# aMazeGarden_schematic.net
KiCad netlist of a schematic drawn in EAGLE
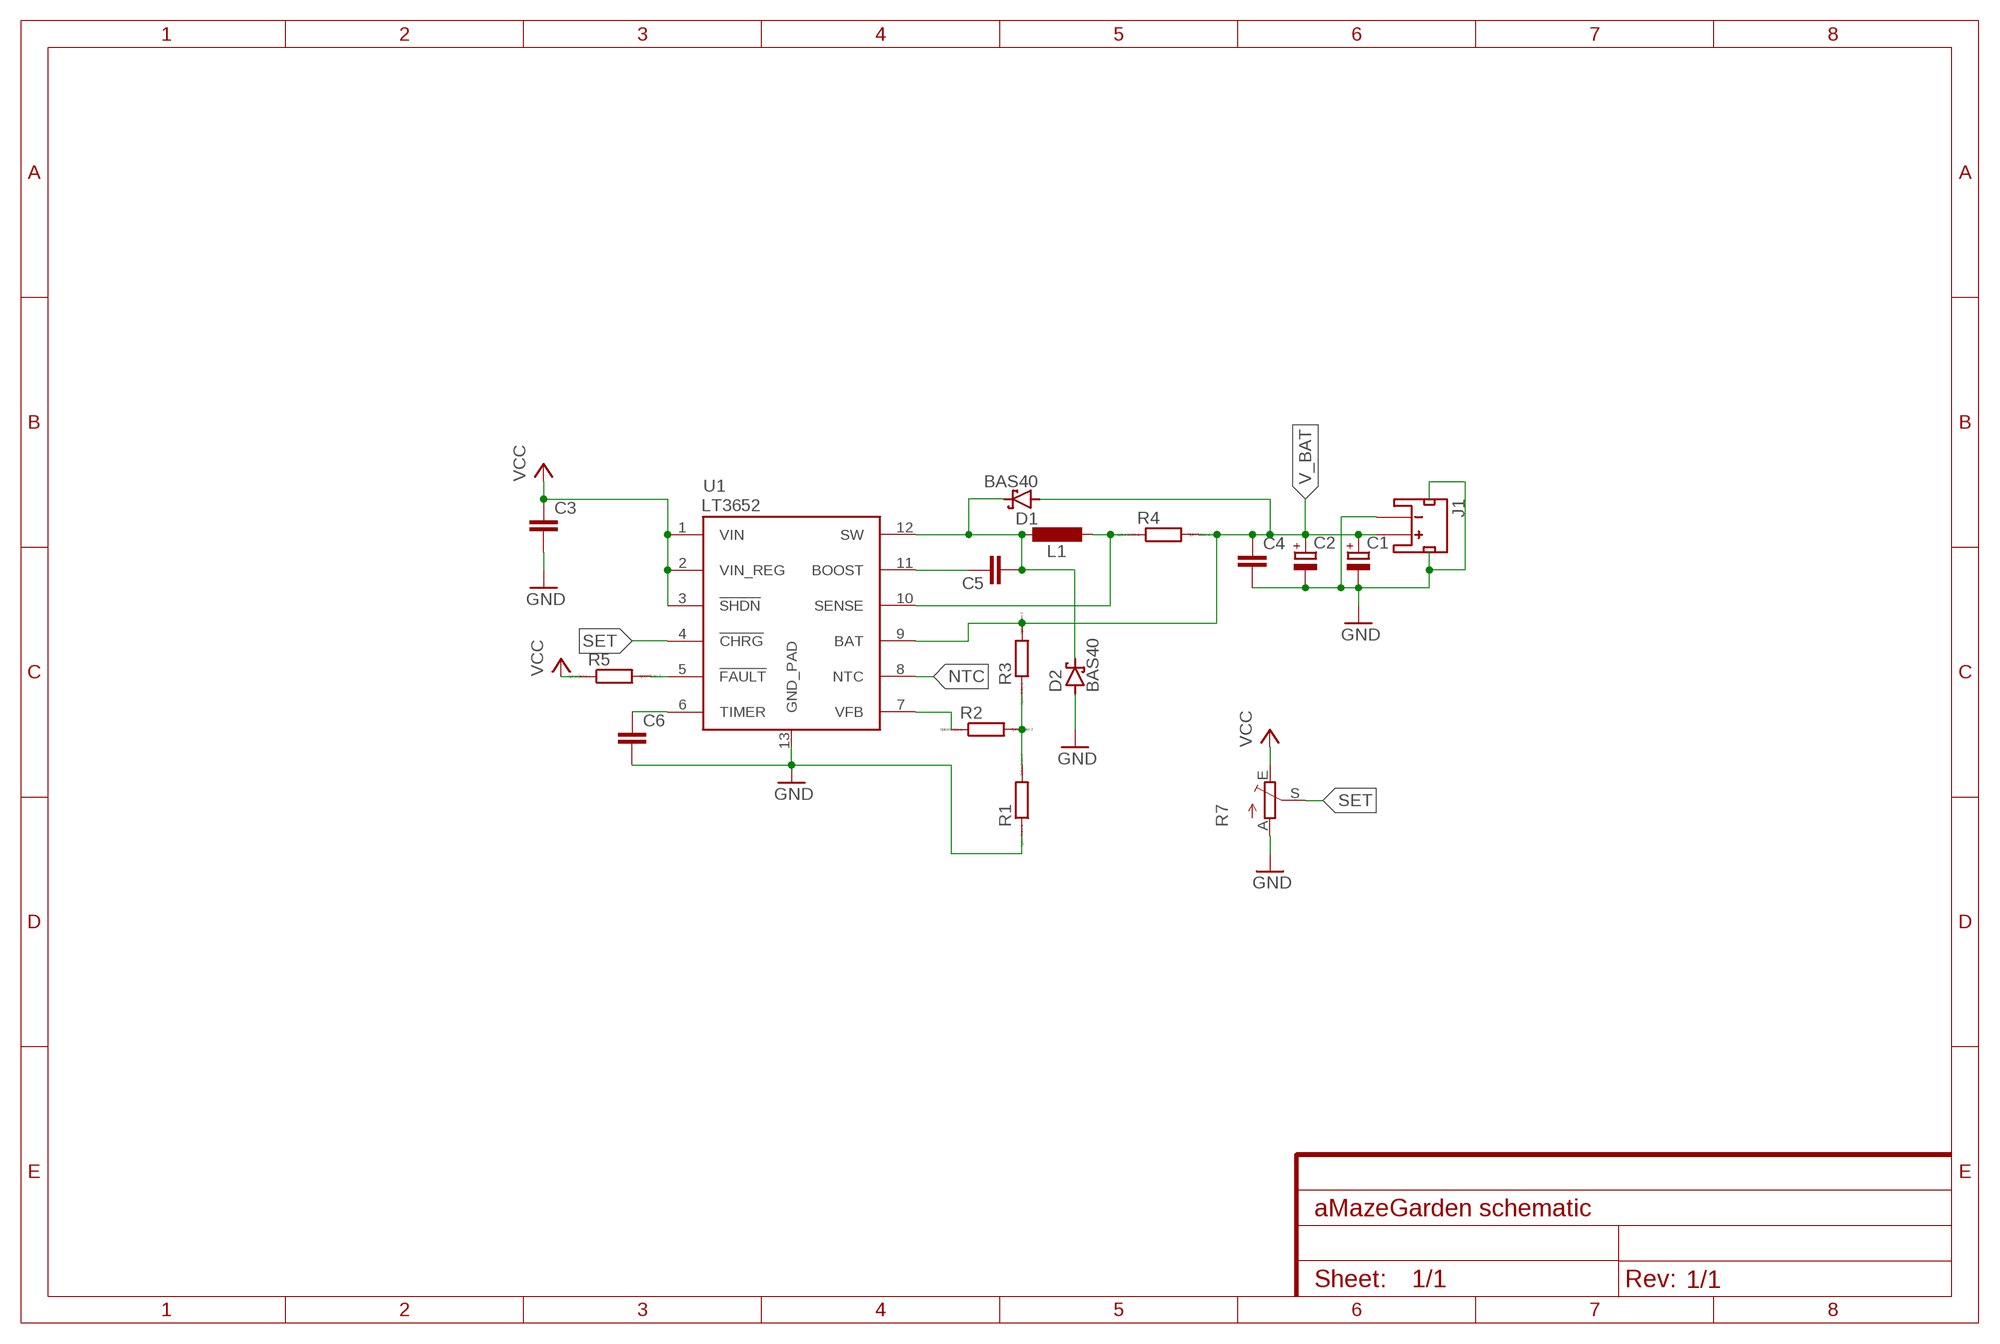
[diagram p0: schematic, sheet 1]

(export (version "E")
  (design (tool "Eeschema 10.0.6"))
  (components
    (comp (ref "C1")
      (value "CPOL-EU085CS-1AR")
      (footprint "eagle-import:085CS_1AR")
      (libsource (lib "eagle-import") (part "CPOL-EU085CS-1AR"))
    )
    (comp (ref "C2")
      (value "CPOL-EU085CS-1AR")
      (footprint "eagle-import:085CS_1AR")
      (libsource (lib "eagle-import") (part "CPOL-EU085CS-1AR"))
    )
    (comp (ref "C3")
      (value "C-EUC0805")
      (footprint "eagle-import:C0805")
      (libsource (lib "eagle-import") (part "C-EUC0805"))
    )
    (comp (ref "C4")
      (value "C-EUC0805")
      (footprint "eagle-import:C0805")
      (libsource (lib "eagle-import") (part "C-EUC0805"))
    )
    (comp (ref "C5")
      (value "C-EUC0805")
      (footprint "eagle-import:C0805")
      (libsource (lib "eagle-import") (part "C-EUC0805"))
    )
    (comp (ref "C6")
      (value "C-EUC0805")
      (footprint "eagle-import:C0805")
      (libsource (lib "eagle-import") (part "C-EUC0805"))
    )
    (comp (ref "D1")
      (value "BAS40")
      (footprint "eagle-import:SOT23")
      (libsource (lib "eagle-import") (part "BAS40"))
    )
    (comp (ref "D2")
      (value "BAS40")
      (footprint "eagle-import:SOT23")
      (libsource (lib "eagle-import") (part "BAS40"))
    )
    (comp (ref "J1")
      (value "JST_2MM_MALE")
      (footprint "eagle-import:JST-2-SMD")
      (libsource (lib "eagle-import") (part "JST_2MM_MALE"))
    )
    (comp (ref "L1")
      (value "L-EUPIS2816")
      (footprint "eagle-import:PIS2816")
      (libsource (lib "eagle-import") (part "L-EUPIS2816"))
    )
    (comp (ref "R1") (value "R") (footprint "eagle-import:R0805") (libsource (lib "eagle-import") (part "R")))
    (comp (ref "R2") (value "R") (footprint "eagle-import:R0805") (libsource (lib "eagle-import") (part "R")))
    (comp (ref "R3") (value "R") (footprint "eagle-import:R0805") (libsource (lib "eagle-import") (part "R")))
    (comp (ref "R4") (value "R") (footprint "eagle-import:R0805") (libsource (lib "eagle-import") (part "R")))
    (comp (ref "R5") (value "R") (footprint "eagle-import:R0805") (libsource (lib "eagle-import") (part "R")))
    (comp (ref "R7")
      (value "TRIM_EU-B25P")
      (footprint "eagle-import:B25P")
      (libsource (lib "eagle-import") (part "TRIM_EU-B25P"))
    )
    (comp (ref "U1")
      (value "LT3652")
      (footprint "eagle-import:MSOP-12_GND")
      (libsource (lib "eagle-import") (part "LT3652"))
    )
  )
  (nets
    (net (code "1") (name "GND") (class "Default")
      (node (ref "C1") (pin "-") (pinfunction "-_-") (pintype "passive"))
      (node (ref "C2") (pin "-") (pinfunction "-_-") (pintype "passive"))
      (node (ref "C3") (pin "2") (pinfunction "2_2") (pintype "passive"))
      (node (ref "C4") (pin "2") (pinfunction "2_2") (pintype "passive"))
      (node (ref "C6") (pin "2") (pinfunction "2_2") (pintype "passive"))
      (node (ref "D2") (pin "1") (pinfunction "A_1") (pintype "passive"))
      (node (ref "J1") (pin "1") (pinfunction "-_1") (pintype "bidirectional"))
      (node (ref "J1") (pin "NC1") (pinfunction "PAD1_NC1") (pintype "bidirectional"))
      (node (ref "J1") (pin "NC2") (pinfunction "PAD2_NC2") (pintype "bidirectional"))
      (node (ref "R1") (pin "1") (pinfunction "1_1") (pintype "passive"))
      (node (ref "R7") (pin "A") (pinfunction "A_A") (pintype "passive"))
      (node (ref "U1") (pin "13") (pinfunction "GND_PAD_13") (pintype "bidirectional"))
    )
    (net (code "2") (name "NTC") (class "Default")
      (node (ref "U1") (pin "8") (pinfunction "NTC_8") (pintype "bidirectional"))
    )
    (net (code "3") (name "Net-(D1-C)") (class "Default")
      (node (ref "C5") (pin "2") (pinfunction "2_2") (pintype "passive"))
      (node (ref "D1") (pin "3") (pinfunction "C_3") (pintype "passive"))
      (node (ref "D2") (pin "3") (pinfunction "C_3") (pintype "passive"))
      (node (ref "L1") (pin "1") (pinfunction "1_1") (pintype "passive"))
      (node (ref "U1") (pin "12") (pinfunction "SW_12") (pintype "bidirectional"))
    )
    (net (code "4") (name "Net-(R1-Pad2)") (class "Default")
      (node (ref "R1") (pin "2") (pinfunction "2_2") (pintype "passive"))
      (node (ref "R2") (pin "2") (pinfunction "2_2") (pintype "passive"))
      (node (ref "R3") (pin "1") (pinfunction "1_1") (pintype "passive"))
    )
    (net (code "5") (name "Net-(U1-BOOST)") (class "Default")
      (node (ref "C5") (pin "1") (pinfunction "1_1") (pintype "passive"))
      (node (ref "U1") (pin "11") (pinfunction "BOOST_11") (pintype "bidirectional"))
    )
    (net (code "6") (name "Net-(U1-SENSE)") (class "Default")
      (node (ref "L1") (pin "2") (pinfunction "2_2") (pintype "passive"))
      (node (ref "R4") (pin "1") (pinfunction "1_1") (pintype "passive"))
      (node (ref "U1") (pin "10") (pinfunction "SENSE_10") (pintype "bidirectional"))
    )
    (net (code "7") (name "Net-(U1-TIMER)") (class "Default")
      (node (ref "C6") (pin "1") (pinfunction "1_1") (pintype "passive"))
      (node (ref "U1") (pin "6") (pinfunction "TIMER_6") (pintype "bidirectional"))
    )
    (net (code "8") (name "Net-(U1-VFB)") (class "Default")
      (node (ref "R2") (pin "1") (pinfunction "1_1") (pintype "passive"))
      (node (ref "U1") (pin "7") (pinfunction "VFB_7") (pintype "bidirectional"))
    )
    (net (code "9") (name "Net-(U1-~{FAULT})") (class "Default")
      (node (ref "R5") (pin "2") (pinfunction "2_2") (pintype "passive"))
      (node (ref "U1") (pin "5") (pinfunction "~{FAULT}_5") (pintype "bidirectional"))
    )
    (net (code "10") (name "SET") (class "Default")
      (node (ref "R7") (pin "S") (pinfunction "S_S") (pintype "passive"))
      (node (ref "U1") (pin "4") (pinfunction "~{CHRG}_4") (pintype "bidirectional"))
    )
    (net (code "11") (name "VCC") (class "Default")
      (node (ref "C3") (pin "1") (pinfunction "1_1") (pintype "passive"))
      (node (ref "R5") (pin "1") (pinfunction "1_1") (pintype "passive"))
      (node (ref "R7") (pin "E") (pinfunction "E_E") (pintype "passive"))
      (node (ref "U1") (pin "1") (pinfunction "VIN_1") (pintype "bidirectional"))
      (node (ref "U1") (pin "2") (pinfunction "VIN_REG_2") (pintype "bidirectional"))
      (node (ref "U1") (pin "3") (pinfunction "~{SHDN}_3") (pintype "bidirectional"))
    )
    (net (code "12") (name "V_BAT") (class "Default")
      (node (ref "C1") (pin "+") (pinfunction "+_+") (pintype "passive"))
      (node (ref "C2") (pin "+") (pinfunction "+_+") (pintype "passive"))
      (node (ref "C4") (pin "1") (pinfunction "1_1") (pintype "passive"))
      (node (ref "D1") (pin "1") (pinfunction "A_1") (pintype "passive"))
      (node (ref "J1") (pin "2") (pinfunction "+_2") (pintype "bidirectional"))
      (node (ref "R3") (pin "2") (pinfunction "2_2") (pintype "passive"))
      (node (ref "R4") (pin "2") (pinfunction "2_2") (pintype "passive"))
      (node (ref "U1") (pin "9") (pinfunction "BAT_9") (pintype "bidirectional"))
    )
  )
)
